# LowLevelv3.net
KiCad netlist of a schematic drawn in EAGLE
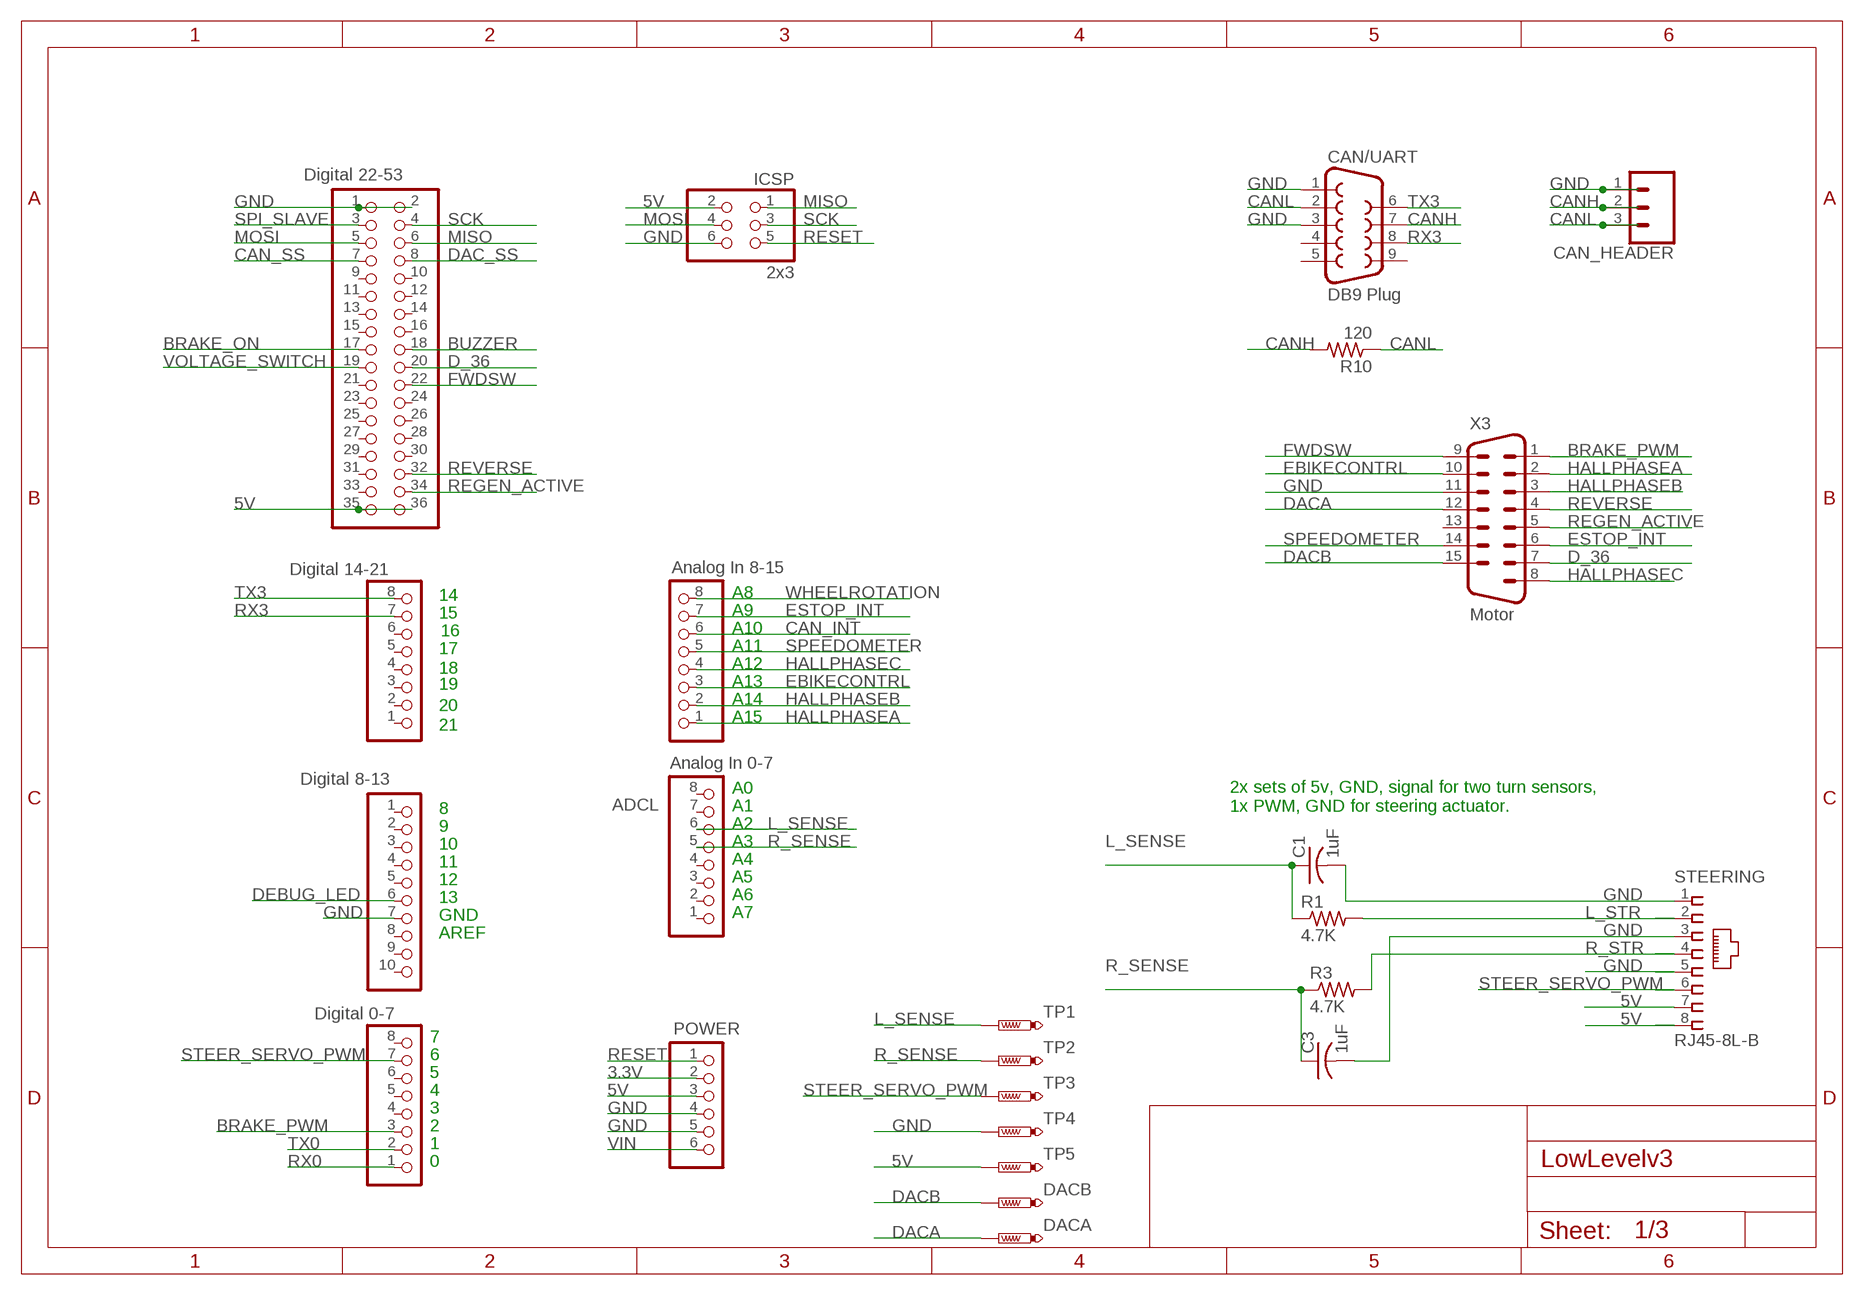
[diagram p0: schematic, sheet 1]
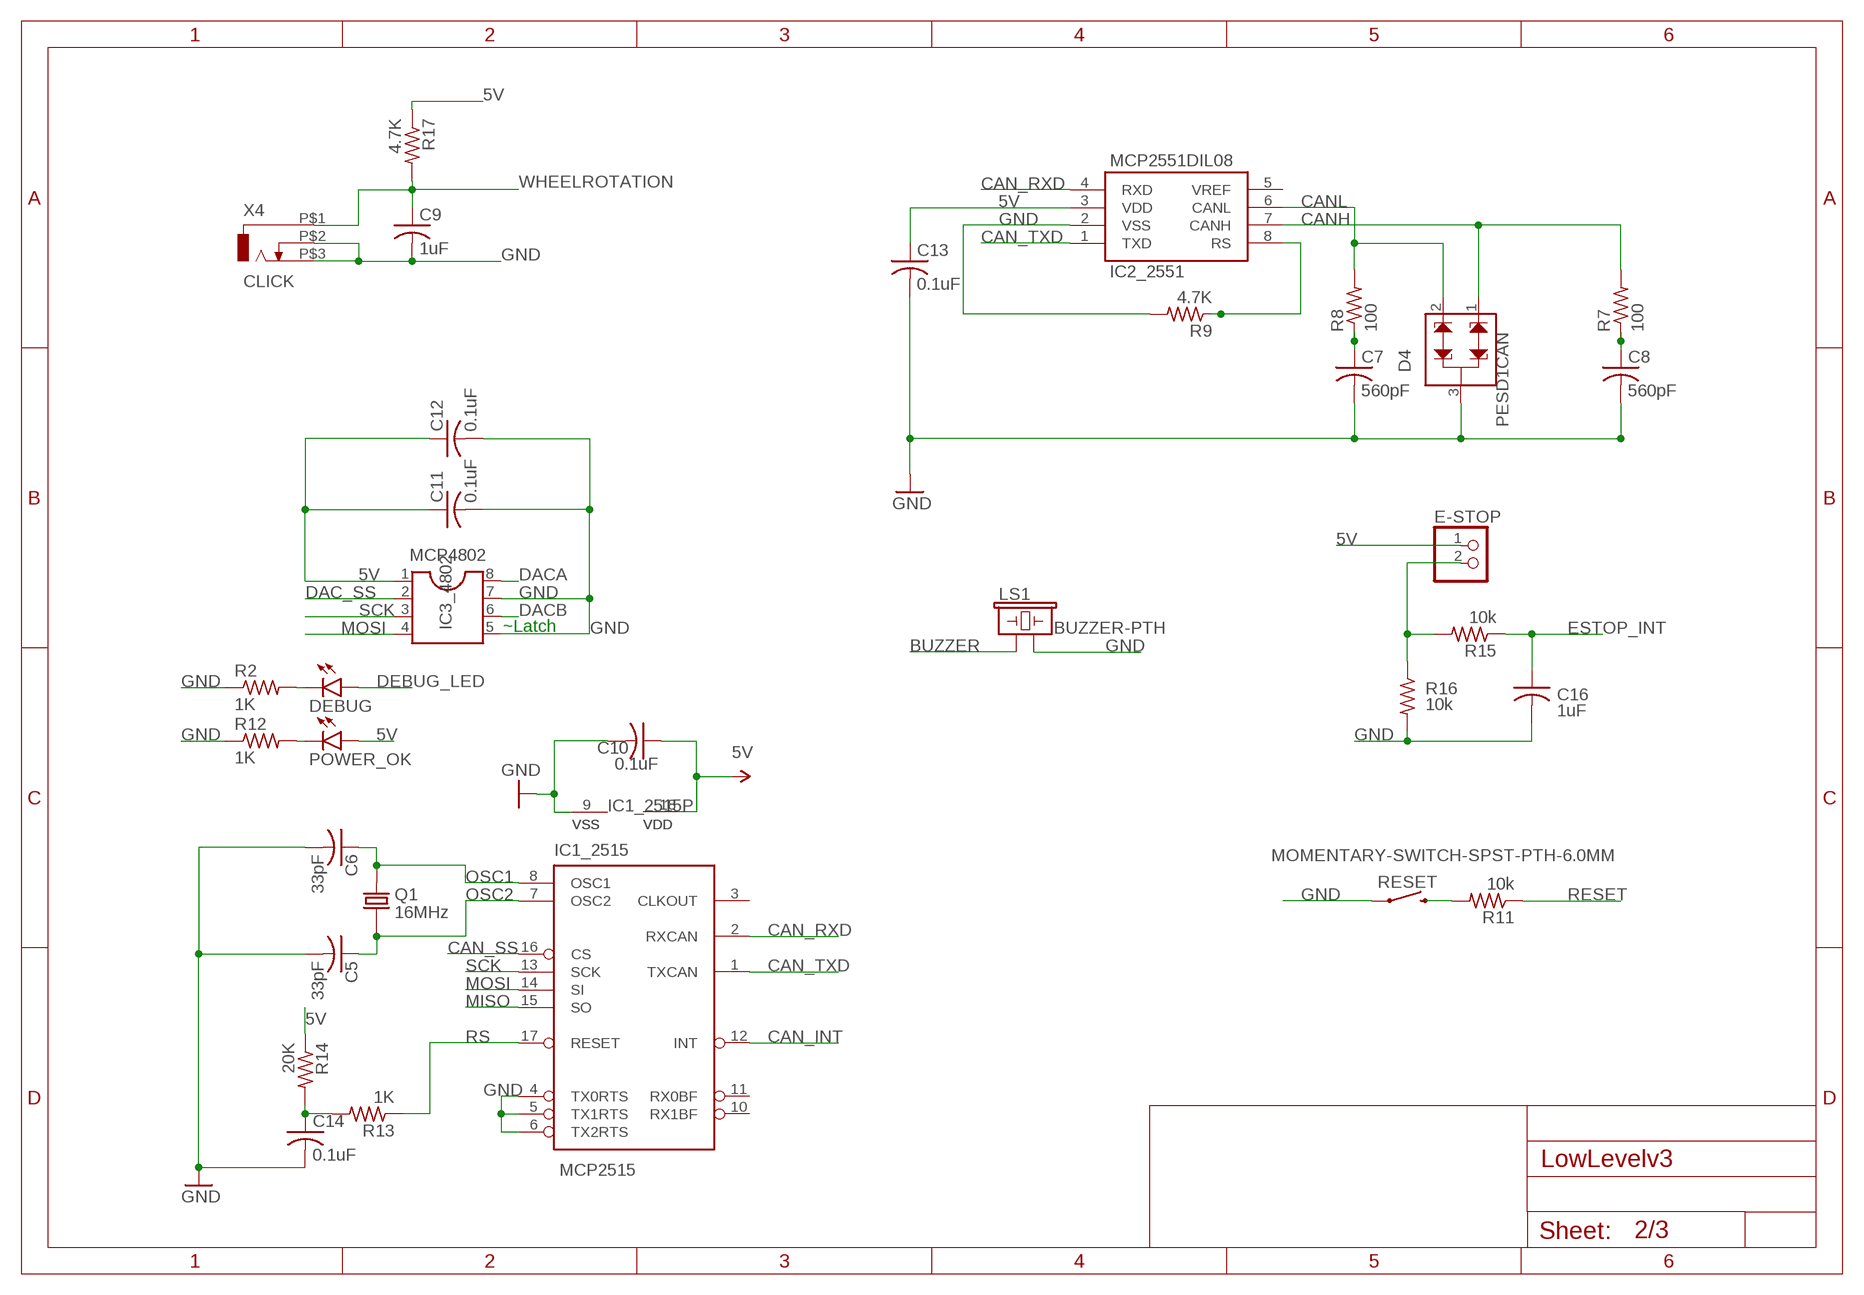
[diagram p1: schematic, sheet 2]
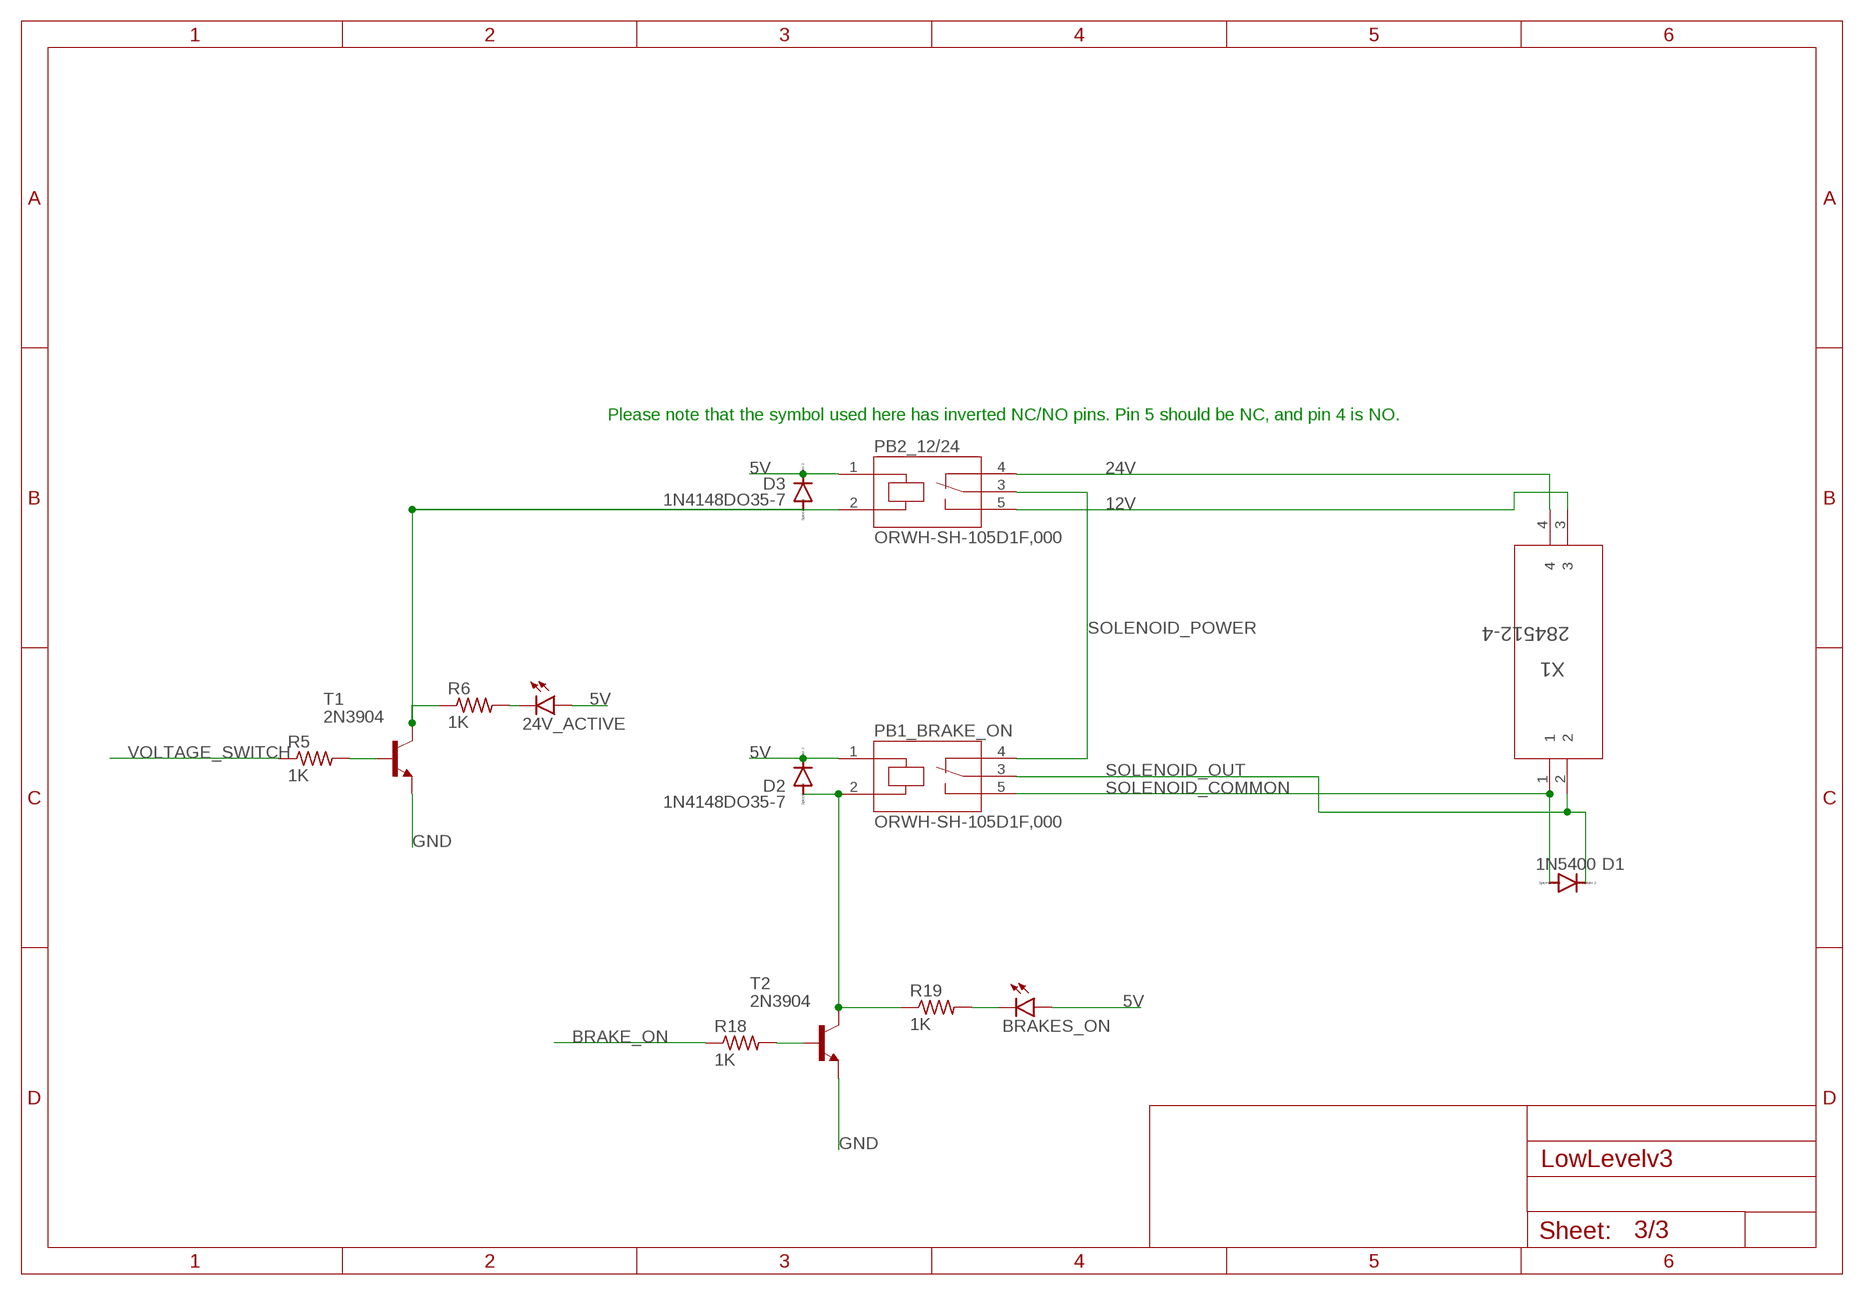
[diagram p2: schematic, sheet 3]

(export (version "E")
  (design (tool "Eeschema 10.0.6"))
  (components
    (comp (ref "ADCH")
      (value "Analog In 8-15")
      (footprint "eagle-import:1X08")
      (libsource (lib "eagle-import") (part "PINHD-1X8"))
    )
    (comp (ref "ADCL")
      (value "Analog In 0-7")
      (footprint "eagle-import:1X08")
      (libsource (lib "eagle-import") (part "PINHD-1X8"))
    )
    (comp (ref "C1")
      (value "1uF")
      (footprint "eagle-import:C1206")
      (libsource (lib "eagle-import") (part "C-USC1206"))
    )
    (comp (ref "C3")
      (value "1uF")
      (footprint "eagle-import:C1206")
      (libsource (lib "eagle-import") (part "C-USC1206"))
    )
    (comp (ref "CAN/UART")
      (value "DB9 Plug")
      (footprint "eagle-import:DB9")
      (fields (field (name "SPICEPREFIX") "X"))
      (libsource (lib "eagle-import") (part "DB9FEMALE"))
    )
    (comp (ref "CAN_HEADER")
      (value "CONN_03-SCREW-5MM")
      (footprint "eagle-import:SCREWTERMINAL-5MM-3")
      (libsource (lib "eagle-import") (part "CONN_03-SCREW-5MM"))
    )
    (comp (ref "DACA")
      (value "PTR1PAD1-17")
      (footprint "eagle-import:P1-17")
      (libsource (lib "eagle-import") (part "PTR1PAD1-17"))
    )
    (comp (ref "DACB")
      (value "PTR1PAD1-17")
      (footprint "eagle-import:P1-17")
      (libsource (lib "eagle-import") (part "PTR1PAD1-17"))
    )
    (comp (ref "DIGITAL_0-7")
      (value "Digital 0-7")
      (footprint "eagle-import:1X08")
      (libsource (lib "eagle-import") (part "PINHD-1X8"))
    )
    (comp (ref "DIGITAL_8-13")
      (value "Digital 8-13")
      (footprint "eagle-import:1X10")
      (libsource (lib "eagle-import") (part "PINHD-1X10"))
    )
    (comp (ref "DIGITAL_14-21")
      (value "Digital 14-21")
      (footprint "eagle-import:1X08")
      (libsource (lib "eagle-import") (part "PINHD-1X8"))
    )
    (comp (ref "ICSP")
      (value "2x3")
      (footprint "eagle-import:2X03")
      (libsource (lib "eagle-import") (part "PINHD-2X3"))
    )
    (comp (ref "MEGA_EXPANSION")
      (value "Digital 22-53")
      (footprint "eagle-import:PINHEAD_2X18")
      (libsource (lib "eagle-import") (part "PINHEAD_PINHD-2X18"))
    )
    (comp (ref "POWER")
      (value "PINHD-1X6")
      (footprint "eagle-import:1X06")
      (libsource (lib "eagle-import") (part "PINHD-1X6"))
    )
    (comp (ref "R1")
      (value "4.7K")
      (footprint "eagle-import:R1206")
      (libsource (lib "eagle-import") (part "R-US_R1206"))
    )
    (comp (ref "R3")
      (value "4.7K")
      (footprint "eagle-import:R1206")
      (libsource (lib "eagle-import") (part "R-US_R1206"))
    )
    (comp (ref "R10")
      (value "120")
      (footprint "eagle-import:R1206")
      (libsource (lib "eagle-import") (part "R-US_R1206"))
    )
    (comp (ref "STEERING")
      (value "RJ45-8L-B")
      (footprint "eagle-import:RJ45-NO-SHIELD")
      (fields (field (name "MF") "TYCO ELECTRONICS"))
      (libsource (lib "eagle-import") (part "RJ45-8L-B"))
    )
    (comp (ref "TP1")
      (value "PTR1PAD1-17")
      (footprint "eagle-import:P1-17")
      (libsource (lib "eagle-import") (part "PTR1PAD1-17"))
    )
    (comp (ref "TP2")
      (value "PTR1PAD1-17")
      (footprint "eagle-import:P1-17")
      (libsource (lib "eagle-import") (part "PTR1PAD1-17"))
    )
    (comp (ref "TP3")
      (value "PTR1PAD1-17")
      (footprint "eagle-import:P1-17")
      (libsource (lib "eagle-import") (part "PTR1PAD1-17"))
    )
    (comp (ref "TP4")
      (value "PTR1PAD1-17")
      (footprint "eagle-import:P1-17")
      (libsource (lib "eagle-import") (part "PTR1PAD1-17"))
    )
    (comp (ref "TP5")
      (value "PTR1PAD1-17")
      (footprint "eagle-import:P1-17")
      (libsource (lib "eagle-import") (part "PTR1PAD1-17"))
    )
    (comp (ref "X3")
      (value "Motor")
      (footprint "eagle-import:182-015-MALE")
      (libsource (lib "eagle-import") (part "M15-182"))
    )
    (comp (ref "C5")
      (value "33pF")
      (footprint "eagle-import:C1206")
      (libsource (lib "eagle-import") (part "C-USC1206"))
    )
    (comp (ref "C6")
      (value "33pF")
      (footprint "eagle-import:C1206")
      (libsource (lib "eagle-import") (part "C-USC1206"))
    )
    (comp (ref "C7")
      (value "560pF")
      (footprint "eagle-import:C1206")
      (libsource (lib "eagle-import") (part "C-USC1206"))
    )
    (comp (ref "C8")
      (value "560pF")
      (footprint "eagle-import:C1206")
      (libsource (lib "eagle-import") (part "C-USC1206"))
    )
    (comp (ref "C9")
      (value "1uF")
      (footprint "eagle-import:C1206")
      (libsource (lib "eagle-import") (part "C-USC1206"))
    )
    (comp (ref "C10")
      (value "0.1uF")
      (footprint "eagle-import:C1206")
      (libsource (lib "eagle-import") (part "C-USC1206"))
    )
    (comp (ref "C11")
      (value "0.1uF")
      (footprint "eagle-import:C1206")
      (libsource (lib "eagle-import") (part "C-USC1206"))
    )
    (comp (ref "C12")
      (value "0.1uF")
      (footprint "eagle-import:C1206")
      (libsource (lib "eagle-import") (part "C-USC1206"))
    )
    (comp (ref "C13")
      (value "0.1uF")
      (footprint "eagle-import:C1206")
      (libsource (lib "eagle-import") (part "C-USC1206"))
    )
    (comp (ref "C14")
      (value "0.1uF")
      (footprint "eagle-import:C1206")
      (libsource (lib "eagle-import") (part "C-USC1206"))
    )
    (comp (ref "C16")
      (value "1uF")
      (footprint "eagle-import:C1206")
      (libsource (lib "eagle-import") (part "C-USC1206"))
    )
    (comp (ref "D4")
      (value "PESD1CAN")
      (footprint "eagle-import:SPARKFUN-DISCRETESEMI_SOT23-3")
      (fields (field (name "SPICEPREFIX") "J"))
      (libsource (lib "eagle-import") (part "PESD1CAN"))
    )
    (comp (ref "DEBUG")
      (value "LED3MM")
      (footprint "eagle-import:LED3MM")
      (libsource (lib "eagle-import") (part "LED3MM"))
    )
    (comp (ref "E-STOP")
      (value "PINHD-1X2")
      (footprint "eagle-import:1X02")
      (libsource (lib "eagle-import") (part "PINHD-1X2"))
    )
    (comp (ref "IC1_2515")
      (value "MCP2515")
      (footprint "eagle-import:DIP18")
      (fields (field (name "SPICEPREFIX") "X"))
      (libsource (lib "eagle-import") (part "MCP2515(MCP2510)P"))
    )
    (comp (ref "IC2_2551")
      (value "MCP2551DIL08")
      (footprint "eagle-import:IC-PACKAGE_DIL08")
      (fields (field (name "SPICEPREFIX") "X"))
      (libsource (lib "eagle-import") (part "MCP2551DIL08"))
    )
    (comp (ref "IC3_4802")
      (value "MCP4802")
      (footprint "eagle-import:DIL08")
      (libsource (lib "eagle-import") (part "DIL8"))
    )
    (comp (ref "LS1")
      (value "BUZZER-PTH")
      (footprint "eagle-import:BUZZER-12MM")
      (libsource (lib "eagle-import") (part "BUZZER-PTH"))
    )
    (comp (ref "POWER_OK")
      (value "LED3MM")
      (footprint "eagle-import:LED3MM")
      (libsource (lib "eagle-import") (part "LED3MM"))
    )
    (comp (ref "Q1")
      (value "16MHz")
      (footprint "eagle-import:XTAL_ECS-160-20-46X")
      (fields
        (field (name "DIGI-KEY_PART_NUMBER") "XC1759-ND")
        (field (name "MF") "ECS Inc.")
        (field (name "MP") "ECS-160-20-46X")
        (field (name "SPICEPREFIX") "B")
      )
      (libsource (lib "eagle-import") (part "ECS-160-20-46X"))
    )
    (comp (ref "R2")
      (value "1K")
      (footprint "eagle-import:R1206")
      (libsource (lib "eagle-import") (part "R-US_R1206"))
    )
    (comp (ref "R7")
      (value "100")
      (footprint "eagle-import:R1206")
      (libsource (lib "eagle-import") (part "R-US_R1206"))
    )
    (comp (ref "R8")
      (value "100")
      (footprint "eagle-import:R1206")
      (libsource (lib "eagle-import") (part "R-US_R1206"))
    )
    (comp (ref "R9")
      (value "4.7K")
      (footprint "eagle-import:R1206")
      (libsource (lib "eagle-import") (part "R-US_R1206"))
    )
    (comp (ref "R11")
      (value "10k")
      (footprint "eagle-import:R1206")
      (libsource (lib "eagle-import") (part "R-US_R1206"))
    )
    (comp (ref "R12")
      (value "1K")
      (footprint "eagle-import:R1206")
      (libsource (lib "eagle-import") (part "R-US_R1206"))
    )
    (comp (ref "R13")
      (value "1K")
      (footprint "eagle-import:R1206")
      (libsource (lib "eagle-import") (part "R-US_R1206"))
    )
    (comp (ref "R14")
      (value "20K")
      (footprint "eagle-import:R1206")
      (libsource (lib "eagle-import") (part "R-US_R1206"))
    )
    (comp (ref "R15")
      (value "10k")
      (footprint "eagle-import:R1206")
      (libsource (lib "eagle-import") (part "R-US_R1206"))
    )
    (comp (ref "R16")
      (value "10k")
      (footprint "eagle-import:R1206")
      (libsource (lib "eagle-import") (part "R-US_R1206"))
    )
    (comp (ref "R17")
      (value "4.7K")
      (footprint "eagle-import:R1206")
      (libsource (lib "eagle-import") (part "R-US_R1206"))
    )
    (comp (ref "RESET")
      (value "MOMENTARY-SWITCH-SPST-PTH-6.0MM")
      (footprint "eagle-import:TACTILE_SWITCH_PTH_6.0MM")
      (libsource (lib "eagle-import") (part "MOMENTARY-SWITCH-SPST-PTH-6.0MM"))
    )
    (comp (ref "X4")
      (value "CLICK")
      (footprint "eagle-import:ODO_JACK")
      (libsource (lib "eagle-import") (part "ODO_JACK"))
    )
    (comp (ref "24V_ACTIVE")
      (value "LED3MM")
      (footprint "eagle-import:LED3MM")
      (libsource (lib "eagle-import") (part "LED3MM"))
    )
    (comp (ref "BRAKES_ON")
      (value "LED3MM")
      (footprint "eagle-import:LED3MM")
      (libsource (lib "eagle-import") (part "LED3MM"))
    )
    (comp (ref "D1")
      (value "1N5400")
      (footprint "eagle-import:DO201-15")
      (libsource (lib "eagle-import") (part "1N5400"))
    )
    (comp (ref "D2")
      (value "1N4148DO35-7")
      (footprint "eagle-import:DO35-7")
      (libsource (lib "eagle-import") (part "1N4148DO35-7"))
    )
    (comp (ref "D3")
      (value "1N4148DO35-7")
      (footprint "eagle-import:DO35-7")
      (libsource (lib "eagle-import") (part "1N4148DO35-7"))
    )
    (comp (ref "PB1_BRAKE_ON")
      (value "ORWH-SH-105D1F,000")
      (footprint "eagle-import:TE_ORWH-SH-105D1F,000")
      (fields (field (name "DIGI-KEY_PART_NUMBER") "PB2032-ND") (field (name "MF") "TE"))
      (libsource (lib "eagle-import") (part "ORWH-SH-105D1F,000"))
    )
    (comp (ref "PB2_12/24")
      (value "ORWH-SH-105D1F,000")
      (footprint "eagle-import:TE_ORWH-SH-105D1F,000")
      (fields (field (name "DIGI-KEY_PART_NUMBER") "PB2032-ND") (field (name "MF") "TE"))
      (libsource (lib "eagle-import") (part "ORWH-SH-105D1F,000"))
    )
    (comp (ref "R5")
      (value "1K")
      (footprint "eagle-import:R1206")
      (libsource (lib "eagle-import") (part "R-US_R1206"))
    )
    (comp (ref "R6")
      (value "1K")
      (footprint "eagle-import:R1206")
      (libsource (lib "eagle-import") (part "R-US_R1206"))
    )
    (comp (ref "R18")
      (value "1K")
      (footprint "eagle-import:R1206")
      (libsource (lib "eagle-import") (part "R-US_R1206"))
    )
    (comp (ref "R19")
      (value "1K")
      (footprint "eagle-import:R1206")
      (libsource (lib "eagle-import") (part "R-US_R1206"))
    )
    (comp (ref "T1")
      (value "2N3904")
      (footprint "eagle-import:TO92")
      (libsource (lib "eagle-import") (part "2N3904"))
    )
    (comp (ref "T2")
      (value "2N3904")
      (footprint "eagle-import:TO92")
      (libsource (lib "eagle-import") (part "2N3904"))
    )
    (comp (ref "X1")
      (value "284512-4")
      (footprint "eagle-import:284512-4")
      (fields (field (name "MANUFACTURER_PART_NUMBER") "2845124"))
      (libsource (lib "eagle-import") (part "284512-4"))
    )
  )
  (nets
    (net (code "1") (name "3.3V") (class "Default")
      (node (ref "POWER") (pin "2") (pinfunction "2_2") (pintype "passive"))
    )
    (net (code "2") (name "5V") (class "Default")
      (node (ref "24V_ACTIVE") (pin "A") (pinfunction "A_A") (pintype "passive"))
      (node (ref "BRAKES_ON") (pin "A") (pinfunction "A_A") (pintype "passive"))
      (node (ref "C10") (pin "1") (pinfunction "1_1") (pintype "passive"))
      (node (ref "C11") (pin "1") (pinfunction "1_1") (pintype "passive"))
      (node (ref "C12") (pin "1") (pinfunction "1_1") (pintype "passive"))
      (node (ref "C13") (pin "1") (pinfunction "1_1") (pintype "passive"))
      (node (ref "D2") (pin "C") (pinfunction "C_C") (pintype "passive"))
      (node (ref "D3") (pin "C") (pinfunction "C_C") (pintype "passive"))
      (node (ref "E-STOP") (pin "1") (pinfunction "1_1") (pintype "passive"))
      (node (ref "IC1_2515") (pin "18") (pinfunction "VDD_18") (pintype "power_in"))
      (node (ref "IC2_2551") (pin "3") (pinfunction "VDD_3") (pintype "bidirectional"))
      (node (ref "IC3_4802") (pin "1") (pinfunction "1_1") (pintype "passive"))
      (node (ref "ICSP") (pin "2") (pinfunction "2_2") (pintype "passive"))
      (node (ref "MEGA_EXPANSION") (pin "35") (pinfunction "35_35") (pintype "passive"))
      (node (ref "MEGA_EXPANSION") (pin "36") (pinfunction "36_36") (pintype "passive"))
      (node (ref "PB1_BRAKE_ON") (pin "1") (pinfunction "C1_1") (pintype "passive"))
      (node (ref "PB2_12/24") (pin "1") (pinfunction "C1_1") (pintype "passive"))
      (node (ref "POWER") (pin "3") (pinfunction "3_3") (pintype "passive"))
      (node (ref "POWER_OK") (pin "A") (pinfunction "A_A") (pintype "passive"))
      (node (ref "R14") (pin "1") (pinfunction "1_1") (pintype "passive"))
      (node (ref "R17") (pin "1") (pinfunction "1_1") (pintype "passive"))
      (node (ref "STEERING") (pin "7") (pinfunction "7_7") (pintype "passive"))
      (node (ref "STEERING") (pin "8") (pinfunction "8_8") (pintype "passive"))
      (node (ref "TP5") (pin "TP") (pinfunction "TP_TP") (pintype "input"))
    )
    (net (code "3") (name "12V") (class "Default")
      (node (ref "PB2_12/24") (pin "5") (pinfunction "NO_5") (pintype "passive"))
      (node (ref "X1") (pin "3") (pinfunction "3_3") (pintype "passive"))
    )
    (net (code "4") (name "24V") (class "Default")
      (node (ref "PB2_12/24") (pin "4") (pinfunction "NC_4") (pintype "passive"))
      (node (ref "X1") (pin "4") (pinfunction "4_4") (pintype "passive"))
    )
    (net (code "5") (name "BRAKE_ON") (class "Default")
      (node (ref "MEGA_EXPANSION") (pin "17") (pinfunction "17_17") (pintype "passive"))
      (node (ref "R18") (pin "1") (pinfunction "1_1") (pintype "passive"))
    )
    (net (code "6") (name "BRAKE_PWM") (class "Default")
      (node (ref "DIGITAL_0-7") (pin "3") (pinfunction "3_3") (pintype "passive"))
      (node (ref "X3") (pin "1") (pinfunction "1_1") (pintype "passive"))
    )
    (net (code "7") (name "BUZZER") (class "Default")
      (node (ref "LS1") (pin "+") (pinfunction "1_+") (pintype "passive"))
      (node (ref "MEGA_EXPANSION") (pin "18") (pinfunction "18_18") (pintype "passive"))
    )
    (net (code "8") (name "CANH") (class "Default")
      (node (ref "CAN/UART") (pin "7") (pinfunction "7_7") (pintype "passive"))
      (node (ref "CAN_HEADER") (pin "2") (pinfunction "2_2") (pintype "passive"))
      (node (ref "D4") (pin "1") (pinfunction "1_1") (pintype "bidirectional"))
      (node (ref "IC2_2551") (pin "7") (pinfunction "CANH_7") (pintype "bidirectional"))
      (node (ref "R10") (pin "2") (pinfunction "2_2") (pintype "passive"))
      (node (ref "R7") (pin "2") (pinfunction "2_2") (pintype "passive"))
    )
    (net (code "9") (name "CANL") (class "Default")
      (node (ref "CAN/UART") (pin "2") (pinfunction "2_2") (pintype "passive"))
      (node (ref "CAN_HEADER") (pin "3") (pinfunction "3_3") (pintype "passive"))
      (node (ref "D4") (pin "2") (pinfunction "2_2") (pintype "bidirectional"))
      (node (ref "IC2_2551") (pin "6") (pinfunction "CANL_6") (pintype "bidirectional"))
      (node (ref "R10") (pin "1") (pinfunction "1_1") (pintype "passive"))
      (node (ref "R8") (pin "2") (pinfunction "2_2") (pintype "passive"))
    )
    (net (code "10") (name "CAN_INT") (class "Default")
      (node (ref "ADCH") (pin "6") (pinfunction "6_6") (pintype "passive"))
      (node (ref "IC1_2515") (pin "12") (pinfunction "INT_12") (pintype "output"))
    )
    (net (code "11") (name "CAN_RXD") (class "Default")
      (node (ref "IC1_2515") (pin "2") (pinfunction "RXCAN_2") (pintype "input"))
      (node (ref "IC2_2551") (pin "4") (pinfunction "RXD_4") (pintype "bidirectional"))
    )
    (net (code "12") (name "CAN_SS") (class "Default")
      (node (ref "IC1_2515") (pin "16") (pinfunction "CS_16") (pintype "input"))
      (node (ref "MEGA_EXPANSION") (pin "7") (pinfunction "7_7") (pintype "passive"))
    )
    (net (code "13") (name "CAN_TXD") (class "Default")
      (node (ref "IC1_2515") (pin "1") (pinfunction "TXCAN_1") (pintype "output"))
      (node (ref "IC2_2551") (pin "1") (pinfunction "TXD_1") (pintype "bidirectional"))
    )
    (net (code "14") (name "DACA") (class "Default")
      (node (ref "DACA") (pin "TP") (pinfunction "TP_TP") (pintype "input"))
      (node (ref "IC3_4802") (pin "8") (pinfunction "8_8") (pintype "passive"))
      (node (ref "X3") (pin "12") (pinfunction "12_12") (pintype "passive"))
    )
    (net (code "15") (name "DACB") (class "Default")
      (node (ref "DACB") (pin "TP") (pinfunction "TP_TP") (pintype "input"))
      (node (ref "IC3_4802") (pin "6") (pinfunction "6_6") (pintype "passive"))
      (node (ref "X3") (pin "15") (pinfunction "15_15") (pintype "passive"))
    )
    (net (code "16") (name "DAC_SS") (class "Default")
      (node (ref "IC3_4802") (pin "2") (pinfunction "2_2") (pintype "passive"))
      (node (ref "MEGA_EXPANSION") (pin "8") (pinfunction "8_8") (pintype "passive"))
    )
    (net (code "17") (name "DEBUG_LED") (class "Default")
      (node (ref "DEBUG") (pin "A") (pinfunction "A_A") (pintype "passive"))
      (node (ref "DIGITAL_8-13") (pin "6") (pinfunction "6_6") (pintype "passive"))
    )
    (net (code "18") (name "D_36") (class "Default")
      (node (ref "MEGA_EXPANSION") (pin "20") (pinfunction "20_20") (pintype "passive"))
      (node (ref "X3") (pin "7") (pinfunction "7_7") (pintype "passive"))
    )
    (net (code "19") (name "EBIKECONTRL") (class "Default")
      (node (ref "ADCH") (pin "3") (pinfunction "3_3") (pintype "passive"))
      (node (ref "X3") (pin "10") (pinfunction "10_10") (pintype "passive"))
    )
    (net (code "20") (name "ESTOP_INT") (class "Default")
      (node (ref "ADCH") (pin "7") (pinfunction "7_7") (pintype "passive"))
      (node (ref "C16") (pin "1") (pinfunction "1_1") (pintype "passive"))
      (node (ref "R15") (pin "1") (pinfunction "1_1") (pintype "passive"))
      (node (ref "X3") (pin "6") (pinfunction "6_6") (pintype "passive"))
    )
    (net (code "21") (name "FWDSW") (class "Default")
      (node (ref "MEGA_EXPANSION") (pin "22") (pinfunction "22_22") (pintype "passive"))
      (node (ref "X3") (pin "9") (pinfunction "9_9") (pintype "passive"))
    )
    (net (code "22") (name "GND") (class "Default")
      (node (ref "C1") (pin "2") (pinfunction "2_2") (pintype "passive"))
      (node (ref "C10") (pin "2") (pinfunction "2_2") (pintype "passive"))
      (node (ref "C11") (pin "2") (pinfunction "2_2") (pintype "passive"))
      (node (ref "C12") (pin "2") (pinfunction "2_2") (pintype "passive"))
      (node (ref "C13") (pin "2") (pinfunction "2_2") (pintype "passive"))
      (node (ref "C14") (pin "2") (pinfunction "2_2") (pintype "passive"))
      (node (ref "C16") (pin "2") (pinfunction "2_2") (pintype "passive"))
      (node (ref "C3") (pin "2") (pinfunction "2_2") (pintype "passive"))
      (node (ref "C5") (pin "2") (pinfunction "2_2") (pintype "passive"))
      (node (ref "C6") (pin "2") (pinfunction "2_2") (pintype "passive"))
      (node (ref "C7") (pin "2") (pinfunction "2_2") (pintype "passive"))
      (node (ref "C8") (pin "2") (pinfunction "2_2") (pintype "passive"))
      (node (ref "C9") (pin "2") (pinfunction "2_2") (pintype "passive"))
      (node (ref "CAN/UART") (pin "1") (pinfunction "1_1") (pintype "passive"))
      (node (ref "CAN/UART") (pin "3") (pinfunction "3_3") (pintype "passive"))
      (node (ref "CAN_HEADER") (pin "1") (pinfunction "1_1") (pintype "passive"))
      (node (ref "D4") (pin "3") (pinfunction "3_3") (pintype "bidirectional"))
      (node (ref "DIGITAL_8-13") (pin "7") (pinfunction "7_7") (pintype "passive"))
      (node (ref "IC1_2515") (pin "4") (pinfunction "TX0RTS_4") (pintype "input"))
      (node (ref "IC1_2515") (pin "5") (pinfunction "TX1RTS_5") (pintype "input"))
      (node (ref "IC1_2515") (pin "6") (pinfunction "TX2RTS_6") (pintype "input"))
      (node (ref "IC1_2515") (pin "9") (pinfunction "VSS_9") (pintype "power_in"))
      (node (ref "IC2_2551") (pin "2") (pinfunction "VSS_2") (pintype "bidirectional"))
      (node (ref "IC3_4802") (pin "5") (pinfunction "5_5") (pintype "passive"))
      (node (ref "IC3_4802") (pin "7") (pinfunction "7_7") (pintype "passive"))
      (node (ref "ICSP") (pin "6") (pinfunction "6_6") (pintype "passive"))
      (node (ref "LS1") (pin "-") (pinfunction "2_-") (pintype "passive"))
      (node (ref "MEGA_EXPANSION") (pin "1") (pinfunction "1_1") (pintype "passive"))
      (node (ref "MEGA_EXPANSION") (pin "2") (pinfunction "2_2") (pintype "passive"))
      (node (ref "POWER") (pin "4") (pinfunction "4_4") (pintype "passive"))
      (node (ref "POWER") (pin "5") (pinfunction "5_5") (pintype "passive"))
      (node (ref "R12") (pin "1") (pinfunction "1_1") (pintype "passive"))
      (node (ref "R16") (pin "2") (pinfunction "2_2") (pintype "passive"))
      (node (ref "R2") (pin "1") (pinfunction "1_1") (pintype "passive"))
      (node (ref "R9") (pin "2") (pinfunction "2_2") (pintype "passive"))
      (node (ref "RESET") (pin "1") (pinfunction "1_1") (pintype "passive"))
      (node (ref "STEERING") (pin "1") (pinfunction "1_1") (pintype "passive"))
      (node (ref "STEERING") (pin "3") (pinfunction "3_3") (pintype "passive"))
      (node (ref "STEERING") (pin "5") (pinfunction "5_5") (pintype "passive"))
      (node (ref "T1") (pin "3") (pinfunction "E_3") (pintype "passive"))
      (node (ref "T2") (pin "3") (pinfunction "E_3") (pintype "passive"))
      (node (ref "TP4") (pin "TP") (pinfunction "TP_TP") (pintype "input"))
      (node (ref "X3") (pin "11") (pinfunction "11_11") (pintype "passive"))
      (node (ref "X4") (pin "P$2") (pinfunction "2_P$2") (pintype "passive"))
      (node (ref "X4") (pin "P$3") (pinfunction "3_P$3") (pintype "passive"))
    )
    (net (code "23") (name "HALLPHASEA") (class "Default")
      (node (ref "ADCH") (pin "1") (pinfunction "1_1") (pintype "passive"))
      (node (ref "X3") (pin "2") (pinfunction "2_2") (pintype "passive"))
    )
    (net (code "24") (name "HALLPHASEB") (class "Default")
      (node (ref "ADCH") (pin "2") (pinfunction "2_2") (pintype "passive"))
      (node (ref "X3") (pin "3") (pinfunction "3_3") (pintype "passive"))
    )
    (net (code "25") (name "HALLPHASEC") (class "Default")
      (node (ref "ADCH") (pin "4") (pinfunction "4_4") (pintype "passive"))
      (node (ref "X3") (pin "8") (pinfunction "8_8") (pintype "passive"))
    )
    (net (code "26") (name "L_SENSE") (class "Default")
      (node (ref "ADCL") (pin "6") (pinfunction "6_6") (pintype "passive"))
      (node (ref "C1") (pin "1") (pinfunction "1_1") (pintype "passive"))
      (node (ref "R1") (pin "1") (pinfunction "1_1") (pintype "passive"))
      (node (ref "TP1") (pin "TP") (pinfunction "TP_TP") (pintype "input"))
    )
    (net (code "27") (name "L_STR") (class "Default")
      (node (ref "R1") (pin "2") (pinfunction "2_2") (pintype "passive"))
      (node (ref "STEERING") (pin "2") (pinfunction "2_2") (pintype "passive"))
    )
    (net (code "28") (name "MISO") (class "Default")
      (node (ref "IC1_2515") (pin "15") (pinfunction "SO_15") (pintype "output"))
      (node (ref "ICSP") (pin "1") (pinfunction "1_1") (pintype "passive"))
      (node (ref "MEGA_EXPANSION") (pin "6") (pinfunction "6_6") (pintype "passive"))
    )
    (net (code "29") (name "MOSI") (class "Default")
      (node (ref "IC1_2515") (pin "14") (pinfunction "SI_14") (pintype "input"))
      (node (ref "IC3_4802") (pin "4") (pinfunction "4_4") (pintype "passive"))
      (node (ref "ICSP") (pin "4") (pinfunction "4_4") (pintype "passive"))
      (node (ref "MEGA_EXPANSION") (pin "5") (pinfunction "5_5") (pintype "passive"))
    )
    (net (code "30") (name "Net-(24V_ACTIVE-C)") (class "Default")
      (node (ref "24V_ACTIVE") (pin "K") (pinfunction "C_K") (pintype "passive"))
      (node (ref "R6") (pin "2") (pinfunction "2_2") (pintype "passive"))
    )
    (net (code "31") (name "Net-(BRAKES_ON-C)") (class "Default")
      (node (ref "BRAKES_ON") (pin "K") (pinfunction "C_K") (pintype "passive"))
      (node (ref "R19") (pin "2") (pinfunction "2_2") (pintype "passive"))
    )
    (net (code "32") (name "Net-(C7-Pad1)") (class "Default")
      (node (ref "C7") (pin "1") (pinfunction "1_1") (pintype "passive"))
      (node (ref "R8") (pin "1") (pinfunction "1_1") (pintype "passive"))
    )
    (net (code "33") (name "Net-(C8-Pad1)") (class "Default")
      (node (ref "C8") (pin "1") (pinfunction "1_1") (pintype "passive"))
      (node (ref "R7") (pin "1") (pinfunction "1_1") (pintype "passive"))
    )
    (net (code "34") (name "Net-(C14-Pad1)") (class "Default")
      (node (ref "C14") (pin "1") (pinfunction "1_1") (pintype "passive"))
      (node (ref "R13") (pin "2") (pinfunction "2_2") (pintype "passive"))
      (node (ref "R14") (pin "2") (pinfunction "2_2") (pintype "passive"))
    )
    (net (code "35") (name "Net-(DEBUG-C)") (class "Default")
      (node (ref "DEBUG") (pin "K") (pinfunction "C_K") (pintype "passive"))
      (node (ref "R2") (pin "2") (pinfunction "2_2") (pintype "passive"))
    )
    (net (code "36") (name "Net-(E-STOP-Pad2)") (class "Default")
      (node (ref "E-STOP") (pin "2") (pinfunction "2_2") (pintype "passive"))
      (node (ref "R15") (pin "2") (pinfunction "2_2") (pintype "passive"))
      (node (ref "R16") (pin "1") (pinfunction "1_1") (pintype "passive"))
    )
    (net (code "37") (name "Net-(IC2_2551-RS)") (class "Default")
      (node (ref "IC2_2551") (pin "8") (pinfunction "RS_8") (pintype "bidirectional"))
      (node (ref "R9") (pin "1") (pinfunction "1_1") (pintype "passive"))
    )
    (net (code "38") (name "Net-(PB1_BRAKE_ON-C2)") (class "Default")
      (node (ref "D2") (pin "A") (pinfunction "A_A") (pintype "passive"))
      (node (ref "PB1_BRAKE_ON") (pin "2") (pinfunction "C2_2") (pintype "passive"))
      (node (ref "R19") (pin "1") (pinfunction "1_1") (pintype "passive"))
      (node (ref "T2") (pin "1") (pinfunction "C_1") (pintype "passive"))
    )
    (net (code "39") (name "Net-(PB2_12/24-C2)") (class "Default")
      (node (ref "D3") (pin "A") (pinfunction "A_A") (pintype "passive"))
      (node (ref "PB2_12/24") (pin "2") (pinfunction "C2_2") (pintype "passive"))
      (node (ref "R6") (pin "1") (pinfunction "1_1") (pintype "passive"))
      (node (ref "T1") (pin "1") (pinfunction "C_1") (pintype "passive"))
    )
    (net (code "40") (name "Net-(POWER_OK-C)") (class "Default")
      (node (ref "POWER_OK") (pin "K") (pinfunction "C_K") (pintype "passive"))
      (node (ref "R12") (pin "2") (pinfunction "2_2") (pintype "passive"))
    )
    (net (code "41") (name "Net-(RESET-2)") (class "Default")
      (node (ref "R11") (pin "2") (pinfunction "2_2") (pintype "passive"))
      (node (ref "RESET") (pin "3") (pinfunction "2_3") (pintype "passive"))
    )
    (net (code "42") (name "Net-(T1-B)") (class "Default")
      (node (ref "R5") (pin "2") (pinfunction "2_2") (pintype "passive"))
      (node (ref "T1") (pin "2") (pinfunction "B_2") (pintype "passive"))
    )
    (net (code "43") (name "Net-(T2-B)") (class "Default")
      (node (ref "R18") (pin "2") (pinfunction "2_2") (pintype "passive"))
      (node (ref "T2") (pin "2") (pinfunction "B_2") (pintype "passive"))
    )
    (net (code "44") (name "OSC1") (class "Default")
      (node (ref "C6") (pin "1") (pinfunction "1_1") (pintype "passive"))
      (node (ref "IC1_2515") (pin "8") (pinfunction "OSC1_8") (pintype "input"))
      (node (ref "Q1") (pin "2") (pinfunction "2_2") (pintype "passive"))
    )
    (net (code "45") (name "OSC2") (class "Default")
      (node (ref "C5") (pin "1") (pinfunction "1_1") (pintype "passive"))
      (node (ref "IC1_2515") (pin "7") (pinfunction "OSC2_7") (pintype "output"))
      (node (ref "Q1") (pin "1") (pinfunction "1_1") (pintype "passive"))
    )
    (net (code "46") (name "REGEN_ACTIVE") (class "Default")
      (node (ref "MEGA_EXPANSION") (pin "34") (pinfunction "34_34") (pintype "passive"))
      (node (ref "X3") (pin "5") (pinfunction "5_5") (pintype "passive"))
    )
    (net (code "47") (name "RESET") (class "Default")
      (node (ref "ICSP") (pin "5") (pinfunction "5_5") (pintype "passive"))
      (node (ref "POWER") (pin "1") (pinfunction "1_1") (pintype "passive"))
      (node (ref "R11") (pin "1") (pinfunction "1_1") (pintype "passive"))
    )
    (net (code "48") (name "REVERSE") (class "Default")
      (node (ref "MEGA_EXPANSION") (pin "32") (pinfunction "32_32") (pintype "passive"))
      (node (ref "X3") (pin "4") (pinfunction "4_4") (pintype "passive"))
    )
    (net (code "49") (name "RS") (class "Default")
      (node (ref "IC1_2515") (pin "17") (pinfunction "RESET_17") (pintype "input"))
      (node (ref "R13") (pin "1") (pinfunction "1_1") (pintype "passive"))
    )
    (net (code "50") (name "RX0") (class "Default")
      (node (ref "DIGITAL_0-7") (pin "1") (pinfunction "1_1") (pintype "passive"))
    )
    (net (code "51") (name "RX3") (class "Default")
      (node (ref "CAN/UART") (pin "8") (pinfunction "8_8") (pintype "passive"))
      (node (ref "DIGITAL_14-21") (pin "7") (pinfunction "7_7") (pintype "passive"))
    )
    (net (code "52") (name "R_SENSE") (class "Default")
      (node (ref "ADCL") (pin "5") (pinfunction "5_5") (pintype "passive"))
      (node (ref "C3") (pin "1") (pinfunction "1_1") (pintype "passive"))
      (node (ref "R3") (pin "1") (pinfunction "1_1") (pintype "passive"))
      (node (ref "TP2") (pin "TP") (pinfunction "TP_TP") (pintype "input"))
    )
    (net (code "53") (name "R_STR") (class "Default")
      (node (ref "R3") (pin "2") (pinfunction "2_2") (pintype "passive"))
      (node (ref "STEERING") (pin "4") (pinfunction "4_4") (pintype "passive"))
    )
    (net (code "54") (name "SCK") (class "Default")
      (node (ref "IC1_2515") (pin "13") (pinfunction "SCK_13") (pintype "input"))
      (node (ref "IC3_4802") (pin "3") (pinfunction "3_3") (pintype "passive"))
      (node (ref "ICSP") (pin "3") (pinfunction "3_3") (pintype "passive"))
      (node (ref "MEGA_EXPANSION") (pin "4") (pinfunction "4_4") (pintype "passive"))
    )
    (net (code "55") (name "SOLENOID_COMMON") (class "Default")
      (node (ref "D1") (pin "A") (pinfunction "A_A") (pintype "passive"))
      (node (ref "PB1_BRAKE_ON") (pin "5") (pinfunction "NO_5") (pintype "passive"))
      (node (ref "X1") (pin "1") (pinfunction "1_1") (pintype "passive"))
    )
    (net (code "56") (name "SOLENOID_OUT") (class "Default")
      (node (ref "D1") (pin "C") (pinfunction "C_C") (pintype "passive"))
      (node (ref "PB1_BRAKE_ON") (pin "3") (pinfunction "C_3") (pintype "passive"))
      (node (ref "X1") (pin "2") (pinfunction "2_2") (pintype "passive"))
    )
    (net (code "57") (name "SOLENOID_POWER") (class "Default")
      (node (ref "PB1_BRAKE_ON") (pin "4") (pinfunction "NC_4") (pintype "passive"))
      (node (ref "PB2_12/24") (pin "3") (pinfunction "C_3") (pintype "passive"))
    )
    (net (code "58") (name "SPEEDOMETER") (class "Default")
      (node (ref "ADCH") (pin "5") (pinfunction "5_5") (pintype "passive"))
      (node (ref "X3") (pin "14") (pinfunction "14_14") (pintype "passive"))
    )
    (net (code "59") (name "SPI_SLAVE") (class "Default")
      (node (ref "MEGA_EXPANSION") (pin "3") (pinfunction "3_3") (pintype "passive"))
    )
    (net (code "60") (name "STEER_SERVO_PWM") (class "Default")
      (node (ref "DIGITAL_0-7") (pin "7") (pinfunction "7_7") (pintype "passive"))
      (node (ref "STEERING") (pin "6") (pinfunction "6_6") (pintype "passive"))
      (node (ref "TP3") (pin "TP") (pinfunction "TP_TP") (pintype "input"))
    )
    (net (code "61") (name "TX0") (class "Default")
      (node (ref "DIGITAL_0-7") (pin "2") (pinfunction "2_2") (pintype "passive"))
    )
    (net (code "62") (name "TX3") (class "Default")
      (node (ref "CAN/UART") (pin "6") (pinfunction "6_6") (pintype "passive"))
      (node (ref "DIGITAL_14-21") (pin "8") (pinfunction "8_8") (pintype "passive"))
    )
    (net (code "63") (name "VIN") (class "Default")
      (node (ref "POWER") (pin "6") (pinfunction "6_6") (pintype "passive"))
    )
    (net (code "64") (name "VOLTAGE_SWITCH") (class "Default")
      (node (ref "MEGA_EXPANSION") (pin "19") (pinfunction "19_19") (pintype "passive"))
      (node (ref "R5") (pin "1") (pinfunction "1_1") (pintype "passive"))
    )
    (net (code "65") (name "WHEELROTATION") (class "Default")
      (node (ref "ADCH") (pin "8") (pinfunction "8_8") (pintype "passive"))
      (node (ref "C9") (pin "1") (pinfunction "1_1") (pintype "passive"))
      (node (ref "R17") (pin "2") (pinfunction "2_2") (pintype "passive"))
      (node (ref "X4") (pin "P$1") (pinfunction "1_P$1") (pintype "passive"))
    )
    (net (code "66") (name "unconnected-(ADCL-Pad1)") (class "Default")
      (node (ref "ADCL") (pin "1") (pinfunction "1_1") (pintype "passive"))
    )
    (net (code "67") (name "unconnected-(ADCL-Pad2)") (class "Default")
      (node (ref "ADCL") (pin "2") (pinfunction "2_2") (pintype "passive"))
    )
    (net (code "68") (name "unconnected-(ADCL-Pad3)") (class "Default")
      (node (ref "ADCL") (pin "3") (pinfunction "3_3") (pintype "passive"))
    )
    (net (code "69") (name "unconnected-(ADCL-Pad4)") (class "Default")
      (node (ref "ADCL") (pin "4") (pinfunction "4_4") (pintype "passive"))
    )
    (net (code "70") (name "unconnected-(ADCL-Pad7)") (class "Default")
      (node (ref "ADCL") (pin "7") (pinfunction "7_7") (pintype "passive"))
    )
    (net (code "71") (name "unconnected-(ADCL-Pad8)") (class "Default")
      (node (ref "ADCL") (pin "8") (pinfunction "8_8") (pintype "passive"))
    )
    (net (code "72") (name "unconnected-(CAN/UART-Pad4)") (class "Default")
      (node (ref "CAN/UART") (pin "4") (pinfunction "4_4") (pintype "passive"))
    )
    (net (code "73") (name "unconnected-(CAN/UART-Pad5)") (class "Default")
      (node (ref "CAN/UART") (pin "5") (pinfunction "5_5") (pintype "passive"))
    )
    (net (code "74") (name "unconnected-(CAN/UART-Pad9)") (class "Default")
      (node (ref "CAN/UART") (pin "9") (pinfunction "9_9") (pintype "passive"))
    )
    (net (code "75") (name "unconnected-(DIGITAL_0-7-Pad4)") (class "Default")
      (node (ref "DIGITAL_0-7") (pin "4") (pinfunction "4_4") (pintype "passive"))
    )
    (net (code "76") (name "unconnected-(DIGITAL_0-7-Pad5)") (class "Default")
      (node (ref "DIGITAL_0-7") (pin "5") (pinfunction "5_5") (pintype "passive"))
    )
    (net (code "77") (name "unconnected-(DIGITAL_0-7-Pad6)") (class "Default")
      (node (ref "DIGITAL_0-7") (pin "6") (pinfunction "6_6") (pintype "passive"))
    )
    (net (code "78") (name "unconnected-(DIGITAL_0-7-Pad8)") (class "Default")
      (node (ref "DIGITAL_0-7") (pin "8") (pinfunction "8_8") (pintype "passive"))
    )
    (net (code "79") (name "unconnected-(DIGITAL_8-13-Pad1)") (class "Default")
      (node (ref "DIGITAL_8-13") (pin "1") (pinfunction "1_1") (pintype "passive"))
    )
    (net (code "80") (name "unconnected-(DIGITAL_8-13-Pad2)") (class "Default")
      (node (ref "DIGITAL_8-13") (pin "2") (pinfunction "2_2") (pintype "passive"))
    )
    (net (code "81") (name "unconnected-(DIGITAL_8-13-Pad3)") (class "Default")
      (node (ref "DIGITAL_8-13") (pin "3") (pinfunction "3_3") (pintype "passive"))
    )
    (net (code "82") (name "unconnected-(DIGITAL_8-13-Pad4)") (class "Default")
      (node (ref "DIGITAL_8-13") (pin "4") (pinfunction "4_4") (pintype "passive"))
    )
    (net (code "83") (name "unconnected-(DIGITAL_8-13-Pad5)") (class "Default")
      (node (ref "DIGITAL_8-13") (pin "5") (pinfunction "5_5") (pintype "passive"))
    )
    (net (code "84") (name "unconnected-(DIGITAL_8-13-Pad8)") (class "Default")
      (node (ref "DIGITAL_8-13") (pin "8") (pinfunction "8_8") (pintype "passive"))
    )
    (net (code "85") (name "unconnected-(DIGITAL_8-13-Pad9)") (class "Default")
      (node (ref "DIGITAL_8-13") (pin "9") (pinfunction "9_9") (pintype "passive"))
    )
    (net (code "86") (name "unconnected-(DIGITAL_8-13-Pad10)") (class "Default")
      (node (ref "DIGITAL_8-13") (pin "10") (pinfunction "10_10") (pintype "passive"))
    )
    (net (code "87") (name "unconnected-(DIGITAL_14-21-Pad1)") (class "Default")
      (node (ref "DIGITAL_14-21") (pin "1") (pinfunction "1_1") (pintype "passive"))
    )
    (net (code "88") (name "unconnected-(DIGITAL_14-21-Pad2)") (class "Default")
      (node (ref "DIGITAL_14-21") (pin "2") (pinfunction "2_2") (pintype "passive"))
    )
    (net (code "89") (name "unconnected-(DIGITAL_14-21-Pad3)") (class "Default")
      (node (ref "DIGITAL_14-21") (pin "3") (pinfunction "3_3") (pintype "passive"))
    )
    (net (code "90") (name "unconnected-(DIGITAL_14-21-Pad4)") (class "Default")
      (node (ref "DIGITAL_14-21") (pin "4") (pinfunction "4_4") (pintype "passive"))
    )
    (net (code "91") (name "unconnected-(DIGITAL_14-21-Pad5)") (class "Default")
      (node (ref "DIGITAL_14-21") (pin "5") (pinfunction "5_5") (pintype "passive"))
    )
    (net (code "92") (name "unconnected-(DIGITAL_14-21-Pad6)") (class "Default")
      (node (ref "DIGITAL_14-21") (pin "6") (pinfunction "6_6") (pintype "passive"))
    )
    (net (code "93") (name "unconnected-(IC1_2515A-CLKOUT-Pad3)") (class "Default")
      (node (ref "IC1_2515") (pin "3") (pinfunction "CLKOUT_3") (pintype "output"))
    )
    (net (code "94") (name "unconnected-(IC1_2515A-RX0BF-Pad11)") (class "Default")
      (node (ref "IC1_2515") (pin "11") (pinfunction "RX0BF_11") (pintype "output"))
    )
    (net (code "95") (name "unconnected-(IC1_2515A-RX1BF-Pad10)") (class "Default")
      (node (ref "IC1_2515") (pin "10") (pinfunction "RX1BF_10") (pintype "output"))
    )
    (net (code "96") (name "unconnected-(IC2_2551-VREF-Pad5)") (class "Default")
      (node (ref "IC2_2551") (pin "5") (pinfunction "VREF_5") (pintype "bidirectional"))
    )
    (net (code "97") (name "unconnected-(MEGA_EXPANSION-Pad9)") (class "Default")
      (node (ref "MEGA_EXPANSION") (pin "9") (pinfunction "9_9") (pintype "passive"))
    )
    (net (code "98") (name "unconnected-(MEGA_EXPANSION-Pad10)") (class "Default")
      (node (ref "MEGA_EXPANSION") (pin "10") (pinfunction "10_10") (pintype "passive"))
    )
    (net (code "99") (name "unconnected-(MEGA_EXPANSION-Pad11)") (class "Default")
      (node (ref "MEGA_EXPANSION") (pin "11") (pinfunction "11_11") (pintype "passive"))
    )
    (net (code "100") (name "unconnected-(MEGA_EXPANSION-Pad12)") (class "Default")
      (node (ref "MEGA_EXPANSION") (pin "12") (pinfunction "12_12") (pintype "passive"))
    )
    (net (code "101") (name "unconnected-(MEGA_EXPANSION-Pad13)") (class "Default")
      (node (ref "MEGA_EXPANSION") (pin "13") (pinfunction "13_13") (pintype "passive"))
    )
    (net (code "102") (name "unconnected-(MEGA_EXPANSION-Pad14)") (class "Default")
      (node (ref "MEGA_EXPANSION") (pin "14") (pinfunction "14_14") (pintype "passive"))
    )
    (net (code "103") (name "unconnected-(MEGA_EXPANSION-Pad15)") (class "Default")
      (node (ref "MEGA_EXPANSION") (pin "15") (pinfunction "15_15") (pintype "passive"))
    )
    (net (code "104") (name "unconnected-(MEGA_EXPANSION-Pad16)") (class "Default")
      (node (ref "MEGA_EXPANSION") (pin "16") (pinfunction "16_16") (pintype "passive"))
    )
    (net (code "105") (name "unconnected-(MEGA_EXPANSION-Pad21)") (class "Default")
      (node (ref "MEGA_EXPANSION") (pin "21") (pinfunction "21_21") (pintype "passive"))
    )
    (net (code "106") (name "unconnected-(MEGA_EXPANSION-Pad23)") (class "Default")
      (node (ref "MEGA_EXPANSION") (pin "23") (pinfunction "23_23") (pintype "passive"))
    )
    (net (code "107") (name "unconnected-(MEGA_EXPANSION-Pad24)") (class "Default")
      (node (ref "MEGA_EXPANSION") (pin "24") (pinfunction "24_24") (pintype "passive"))
    )
    (net (code "108") (name "unconnected-(MEGA_EXPANSION-Pad25)") (class "Default")
      (node (ref "MEGA_EXPANSION") (pin "25") (pinfunction "25_25") (pintype "passive"))
    )
    (net (code "109") (name "unconnected-(MEGA_EXPANSION-Pad26)") (class "Default")
      (node (ref "MEGA_EXPANSION") (pin "26") (pinfunction "26_26") (pintype "passive"))
    )
    (net (code "110") (name "unconnected-(MEGA_EXPANSION-Pad27)") (class "Default")
      (node (ref "MEGA_EXPANSION") (pin "27") (pinfunction "27_27") (pintype "passive"))
    )
    (net (code "111") (name "unconnected-(MEGA_EXPANSION-Pad28)") (class "Default")
      (node (ref "MEGA_EXPANSION") (pin "28") (pinfunction "28_28") (pintype "passive"))
    )
    (net (code "112") (name "unconnected-(MEGA_EXPANSION-Pad29)") (class "Default")
      (node (ref "MEGA_EXPANSION") (pin "29") (pinfunction "29_29") (pintype "passive"))
    )
    (net (code "113") (name "unconnected-(MEGA_EXPANSION-Pad30)") (class "Default")
      (node (ref "MEGA_EXPANSION") (pin "30") (pinfunction "30_30") (pintype "passive"))
    )
    (net (code "114") (name "unconnected-(MEGA_EXPANSION-Pad31)") (class "Default")
      (node (ref "MEGA_EXPANSION") (pin "31") (pinfunction "31_31") (pintype "passive"))
    )
    (net (code "115") (name "unconnected-(MEGA_EXPANSION-Pad33)") (class "Default")
      (node (ref "MEGA_EXPANSION") (pin "33") (pinfunction "33_33") (pintype "passive"))
    )
    (net (code "116") (name "unconnected-(X3-Pad13)") (class "Default")
      (node (ref "X3") (pin "13") (pinfunction "13_13") (pintype "passive"))
    )
  )
)
